# Ethernet1_RMII.net
KiCad netlist of a schematic drawn in Altium Designer
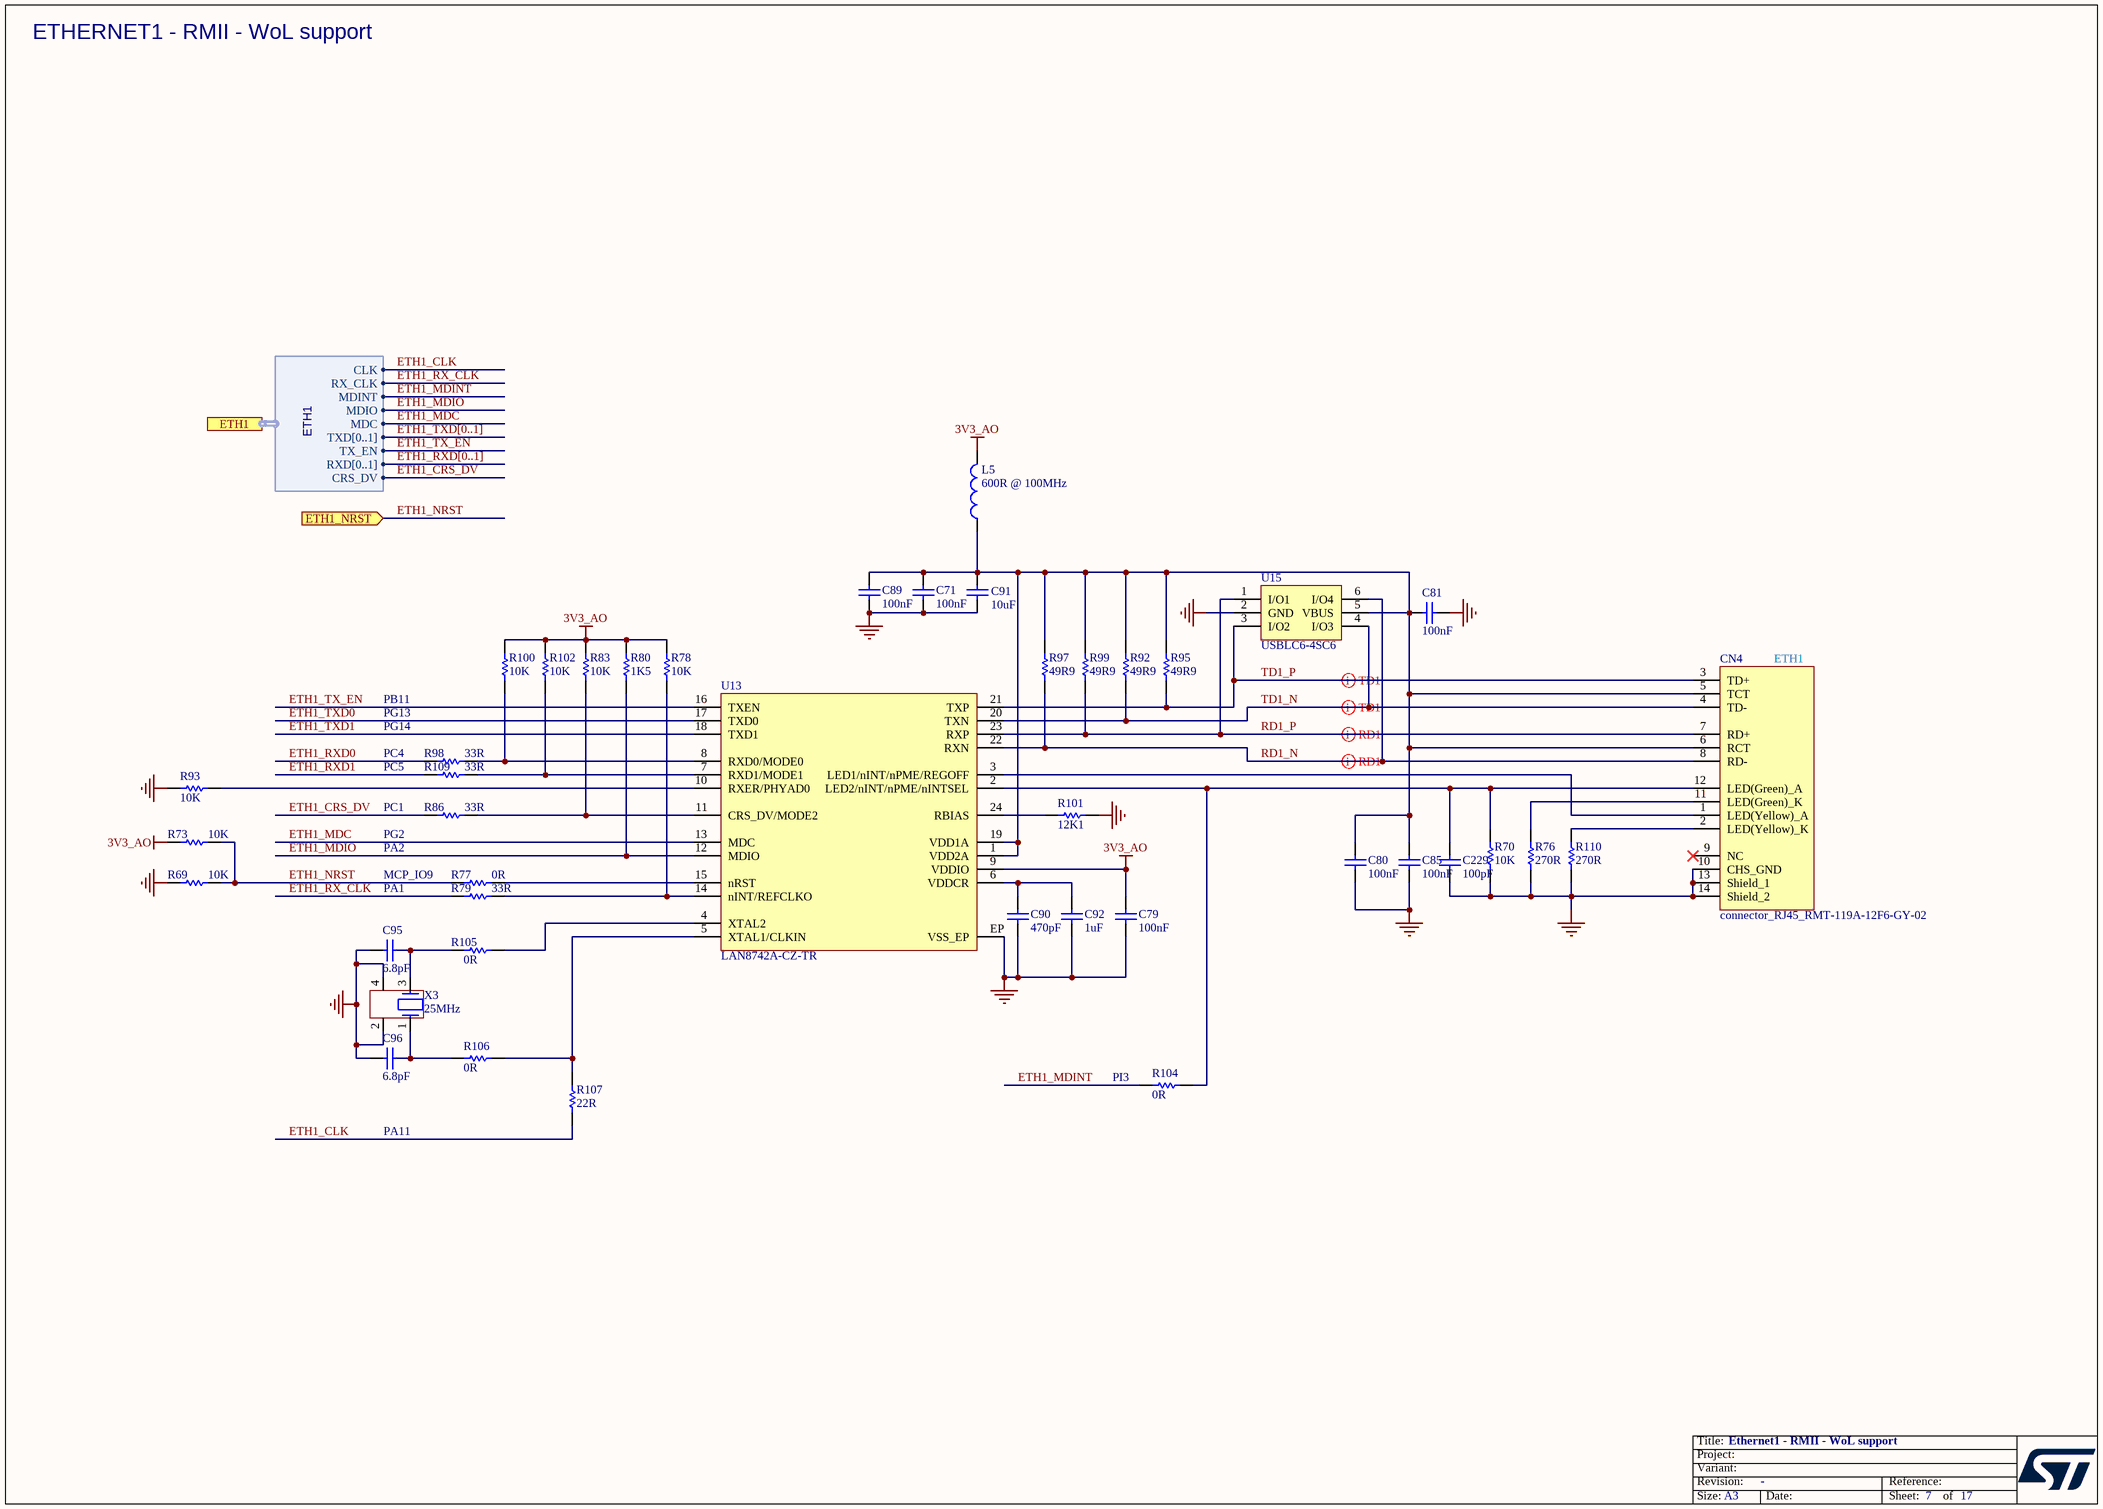
[diagram p0: Ethernet1_RMII.SchDoc]

(export (version "E")
  (design (tool "Eeschema 10.0.6"))
  (components
    (comp (ref "C71")
      (value "100nF")
      (footprint "C0402")
      (description "Capacitor, MLCC, 100nF, 16V, X7R, +/-10%, 0402, T=0.5mm")
      (fields
        (field (name "INTERNAL_PART_NUMBER") "MCD-00006")
        (field (name "MANUFACTURER_PART_NUMBER") "CC0402KRX7R7BB104")
      )
      (libsource (lib "MCD_PARTS_database") (part "Capacitor"))
    )
    (comp (ref "C79")
      (value "100nF")
      (footprint "C0402")
      (description "Capacitor, MLCC, 100nF, 16V, X7R, +/-10%, 0402, T=0.5mm")
      (fields
        (field (name "INTERNAL_PART_NUMBER") "MCD-00006")
        (field (name "MANUFACTURER_PART_NUMBER") "CC0402KRX7R7BB104")
      )
      (libsource (lib "MCD_PARTS_database") (part "Capacitor"))
    )
    (comp (ref "C80")
      (value "100nF")
      (footprint "C0402")
      (description "Capacitor, MLCC, 100nF, 16V, X7R, +/-10%, 0402, T=0.5mm")
      (fields
        (field (name "INTERNAL_PART_NUMBER") "MCD-00006")
        (field (name "MANUFACTURER_PART_NUMBER") "CC0402KRX7R7BB104")
      )
      (libsource (lib "MCD_PARTS_database") (part "Capacitor"))
    )
    (comp (ref "C81")
      (value "100nF")
      (footprint "C0402")
      (description "Capacitor, MLCC, 100nF, 16V, X7R, +/-10%, 0402, T=0.5mm")
      (fields
        (field (name "INTERNAL_PART_NUMBER") "MCD-00006")
        (field (name "MANUFACTURER_PART_NUMBER") "CC0402KRX7R7BB104")
      )
      (libsource (lib "MCD_PARTS_database") (part "Capacitor"))
    )
    (comp (ref "C85")
      (value "100nF")
      (footprint "C0402")
      (description "Capacitor, MLCC, 100nF, 16V, X7R, +/-10%, 0402, T=0.5mm")
      (fields
        (field (name "INTERNAL_PART_NUMBER") "MCD-00006")
        (field (name "MANUFACTURER_PART_NUMBER") "CC0402KRX7R7BB104")
      )
      (libsource (lib "MCD_PARTS_database") (part "Capacitor"))
    )
    (comp (ref "C89")
      (value "100nF")
      (footprint "C0402")
      (description "Capacitor, MLCC, 100nF, 16V, X7R, +/-10%, 0402, T=0.5mm")
      (fields
        (field (name "INTERNAL_PART_NUMBER") "MCD-00006")
        (field (name "MANUFACTURER_PART_NUMBER") "CC0402KRX7R7BB104")
      )
      (libsource (lib "MCD_PARTS_database") (part "Capacitor"))
    )
    (comp (ref "C90")
      (value "470pF")
      (footprint "C0402")
      (description "Capacitor, MLCC, 470pF, 50V, NPO, +/-5%, 0402, T=0.5mm")
      (fields
        (field (name "INTERNAL_PART_NUMBER") "MCD-00724")
        (field (name "MANUFACTURER_PART_NUMBER") "CC0402JRNPO9BN471")
      )
      (libsource (lib "MCD_PARTS_database") (part "Capacitor"))
    )
    (comp (ref "C91")
      (value "10uF")
      (footprint "C0603")
      (description "Capacitor, MLCC, 10uF, 10V, X5R, +/-10%, 0603, T=0.8mm")
      (fields
        (field (name "INTERNAL_PART_NUMBER") "MCD-00099")
        (field (name "MANUFACTURER_PART_NUMBER") "GRM188R61A106KE69D")
      )
      (libsource (lib "MCD_PARTS_database") (part "Capacitor"))
    )
    (comp (ref "C92")
      (value "1uF")
      (footprint "C0201_MURATA_GRM033_H0P3")
      (description "Capacitor, MLCC, 1uF, 6.3V, X5R, +/-20%, 0201, T=0,3mm")
      (fields
        (field (name "INTERNAL_PART_NUMBER") "MCD-02377")
        (field (name "MANUFACTURER_PART_NUMBER") "GRM033R60J105MEA2")
      )
      (libsource (lib "MCD_PARTS_database") (part "Capacitor"))
    )
    (comp (ref "C95")
      (value "6.8pF")
      (footprint "C0402")
      (description "Capacitor, MLCC, 6.8pF, 50V, NPO, +/-0.25pF, 0402, T=0.5mm")
      (fields
        (field (name "INTERNAL_PART_NUMBER") "MCD-00674")
        (field (name "MANUFACTURER_PART_NUMBER") "CC0402CRNPO9BN6R8")
      )
      (libsource (lib "MCD_PARTS_database") (part "Capacitor"))
    )
    (comp (ref "C96")
      (value "6.8pF")
      (footprint "C0402")
      (description "Capacitor, MLCC, 6.8pF, 50V, NPO, +/-0.25pF, 0402, T=0.5mm")
      (fields
        (field (name "INTERNAL_PART_NUMBER") "MCD-00674")
        (field (name "MANUFACTURER_PART_NUMBER") "CC0402CRNPO9BN6R8")
      )
      (libsource (lib "MCD_PARTS_database") (part "Capacitor"))
    )
    (comp (ref "C229")
      (value "100pF")
      (footprint "C0402")
      (description "Capacitor, MLCC, 100pF, 50V, NPO, +/-5%, 0402, T=0.5mm")
      (fields
        (field (name "INTERNAL_PART_NUMBER") "MCD-00205")
        (field (name "MANUFACTURER_PART_NUMBER") "CC0402JRNPO9BN101")
      )
      (libsource (lib "MCD_PARTS_database") (part "Capacitor"))
    )
    (comp (ref "CN4")
      (value "connector_RJ45_RMT-119A-12F6-GY-02")
      (footprint "CON_RJ45_PHC_RMT-119A-12F6-GY-02")
      (description "connector_RJ45, 10/100 Ethernet integrated MAG with integrate Green and Yellow LED, T= 13.61mm")
      (fields (field (name "INTERNAL_PART_NUMBER") "MCD-02475") (field (name "MANUFACTURER") "PENGHUI"))
      (libsource (lib "MCD_PARTS_database") (part "RJ45_RTS-119A-12F6-GY-02"))
    )
    (comp (ref "L5")
      (value "600R @ 100MHz")
      (footprint "L0603")
      (description "Ferrite bead, 600R @1 00MHz, +/-25%, 350mA, 0R5, 0603, T=0.8mm")
      (fields
        (field (name "INTERNAL_PART_NUMBER") "MCD-00047")
        (field (name "MANUFACTURER_PART_NUMBER") "FCM1608KF-601T03")
      )
      (libsource (lib "MCD_PARTS_database") (part "BEAD"))
    )
    (comp (ref "R69")
      (value "10K")
      (footprint "R0402")
      (description "Resistor, 10K, 0402, +/-1%, 1/16W")
      (fields
        (field (name "INTERNAL_PART_NUMBER") "MCD-00053")
        (field (name "MANUFACTURER_PART_NUMBER") "RC0402FR-0710KL")
      )
      (libsource (lib "MCD_PARTS_database") (part "Resistor"))
    )
    (comp (ref "R70")
      (value "10K")
      (footprint "R0402")
      (description "Resistor, 10K, 0402, +/-1%, 1/16W")
      (fields
        (field (name "INTERNAL_PART_NUMBER") "MCD-00053")
        (field (name "MANUFACTURER_PART_NUMBER") "RC0402FR-0710KL")
      )
      (libsource (lib "MCD_PARTS_database") (part "Resistor"))
    )
    (comp (ref "R73")
      (value "10K")
      (footprint "R0402")
      (description "Resistor, 10K, 0402, +/-1%, 1/16W")
      (fields
        (field (name "INTERNAL_PART_NUMBER") "MCD-00053")
        (field (name "MANUFACTURER_PART_NUMBER") "RC0402FR-0710KL")
      )
      (libsource (lib "MCD_PARTS_database") (part "Resistor"))
    )
    (comp (ref "R76")
      (value "270R")
      (footprint "R0402")
      (description "Resistor, 270R, 0402, +/-1%, 1/16W")
      (fields
        (field (name "INTERNAL_PART_NUMBER") "MCD-00441")
        (field (name "MANUFACTURER_PART_NUMBER") "RC0402FR-07270RL")
      )
      (libsource (lib "MCD_PARTS_database") (part "Resistor"))
    )
    (comp (ref "R77")
      (value "0R")
      (footprint "R0402")
      (description "Resistor, 0R, 0402, +/-5%, 1/16W")
      (fields (field (name "INTERNAL_PART_NUMBER") "MCD-00052") (field (name "MANUFACTURER") "YAGEO"))
      (libsource (lib "MCD_PARTS_database") (part "Resistor"))
    )
    (comp (ref "R78")
      (value "10K")
      (footprint "R0402")
      (description "Resistor, 10K, 0402, +/-1%, 1/16W")
      (fields
        (field (name "INTERNAL_PART_NUMBER") "MCD-00053")
        (field (name "MANUFACTURER_PART_NUMBER") "RC0402FR-0710KL")
      )
      (libsource (lib "MCD_PARTS_database") (part "Resistor"))
    )
    (comp (ref "R79")
      (value "33R")
      (footprint "R0402")
      (description "Resistor, 33R, 0402, +/-1%, 1/16W")
      (fields
        (field (name "INTERNAL_PART_NUMBER") "MCD-00455")
        (field (name "MANUFACTURER_PART_NUMBER") "RC0402FR-0733RL")
      )
      (libsource (lib "MCD_PARTS_database") (part "Resistor"))
    )
    (comp (ref "R80")
      (value "1K5")
      (footprint "R0402")
      (description "Resistor, 1K5, 0402, +/-1%, 1/16W")
      (fields
        (field (name "INTERNAL_PART_NUMBER") "MCD-00068")
        (field (name "MANUFACTURER_PART_NUMBER") "RC0402FR-071K5L")
      )
      (libsource (lib "MCD_PARTS_database") (part "Resistor"))
    )
    (comp (ref "R83")
      (value "10K")
      (footprint "R0402")
      (description "Resistor, 10K, 0402, +/-1%, 1/16W")
      (fields
        (field (name "INTERNAL_PART_NUMBER") "MCD-00053")
        (field (name "MANUFACTURER_PART_NUMBER") "RC0402FR-0710KL")
      )
      (libsource (lib "MCD_PARTS_database") (part "Resistor"))
    )
    (comp (ref "R86")
      (value "33R")
      (footprint "R0402")
      (description "Resistor, 33R, 0402, +/-1%, 1/16W")
      (fields
        (field (name "INTERNAL_PART_NUMBER") "MCD-00455")
        (field (name "MANUFACTURER_PART_NUMBER") "RC0402FR-0733RL")
      )
      (libsource (lib "MCD_PARTS_database") (part "Resistor"))
    )
    (comp (ref "R92")
      (value "49R9")
      (footprint "R0402")
      (description "Resistor, 49R9, 0402, +/-1%, 1/16W")
      (fields
        (field (name "INTERNAL_PART_NUMBER") "MCD-00565")
        (field (name "MANUFACTURER_PART_NUMBER") "RC0402FR-0749R9L")
      )
      (libsource (lib "MCD_PARTS_database") (part "Resistor"))
    )
    (comp (ref "R93")
      (value "10K")
      (footprint "R0402")
      (description "Resistor, 10K, 0402, +/-1%, 1/16W")
      (fields
        (field (name "INTERNAL_PART_NUMBER") "MCD-00053")
        (field (name "MANUFACTURER_PART_NUMBER") "RC0402FR-0710KL")
      )
      (libsource (lib "MCD_PARTS_database") (part "Resistor"))
    )
    (comp (ref "R95")
      (value "49R9")
      (footprint "R0402")
      (description "Resistor, 49R9, 0402, +/-1%, 1/16W")
      (fields
        (field (name "INTERNAL_PART_NUMBER") "MCD-00565")
        (field (name "MANUFACTURER_PART_NUMBER") "RC0402FR-0749R9L")
      )
      (libsource (lib "MCD_PARTS_database") (part "Resistor"))
    )
    (comp (ref "R97")
      (value "49R9")
      (footprint "R0402")
      (description "Resistor, 49R9, 0402, +/-1%, 1/16W")
      (fields
        (field (name "INTERNAL_PART_NUMBER") "MCD-00565")
        (field (name "MANUFACTURER_PART_NUMBER") "RC0402FR-0749R9L")
      )
      (libsource (lib "MCD_PARTS_database") (part "Resistor"))
    )
    (comp (ref "R98")
      (value "33R")
      (footprint "R0402")
      (description "Resistor, 33R, 0402, +/-1%, 1/16W")
      (fields
        (field (name "INTERNAL_PART_NUMBER") "MCD-00455")
        (field (name "MANUFACTURER_PART_NUMBER") "RC0402FR-0733RL")
      )
      (libsource (lib "MCD_PARTS_database") (part "Resistor"))
    )
    (comp (ref "R99")
      (value "49R9")
      (footprint "R0402")
      (description "Resistor, 49R9, 0402, +/-1%, 1/16W")
      (fields
        (field (name "INTERNAL_PART_NUMBER") "MCD-00565")
        (field (name "MANUFACTURER_PART_NUMBER") "RC0402FR-0749R9L")
      )
      (libsource (lib "MCD_PARTS_database") (part "Resistor"))
    )
    (comp (ref "R100")
      (value "10K")
      (footprint "R0402")
      (description "Resistor, 10K, 0402, +/-1%, 1/16W")
      (fields
        (field (name "INTERNAL_PART_NUMBER") "MCD-00053")
        (field (name "MANUFACTURER_PART_NUMBER") "RC0402FR-0710KL")
      )
      (libsource (lib "MCD_PARTS_database") (part "Resistor"))
    )
    (comp (ref "R101")
      (value "12K1")
      (footprint "R0402")
      (description "Resistor, 12K1, 0402, +/-1%, 1/16W")
      (fields
        (field (name "INTERNAL_PART_NUMBER") "MCD-00723")
        (field (name "MANUFACTURER_PART_NUMBER") "RC0402FR-0712K1L")
      )
      (libsource (lib "MCD_PARTS_database") (part "Resistor"))
    )
    (comp (ref "R102")
      (value "10K")
      (footprint "R0402")
      (description "Resistor, 10K, 0402, +/-1%, 1/16W")
      (fields
        (field (name "INTERNAL_PART_NUMBER") "MCD-00053")
        (field (name "MANUFACTURER_PART_NUMBER") "RC0402FR-0710KL")
      )
      (libsource (lib "MCD_PARTS_database") (part "Resistor"))
    )
    (comp (ref "R104")
      (value "0R")
      (footprint "R0402")
      (description "Resistor, 0R, 0402, +/-5%, 1/16W")
      (fields
        (field (name "INTERNAL_PART_NUMBER") "MCD-00052")
        (field (name "MANUFACTURER_PART_NUMBER") "RC0402JR-070RL")
      )
      (libsource (lib "MCD_PARTS_database") (part "Resistor"))
    )
    (comp (ref "R105")
      (value "0R")
      (footprint "R0402")
      (description "Resistor, 0R, 0402, +/-5%, 1/16W")
      (fields
        (field (name "INTERNAL_PART_NUMBER") "MCD-00052")
        (field (name "MANUFACTURER_PART_NUMBER") "RC0402JR-070RL")
      )
      (libsource (lib "MCD_PARTS_database") (part "Resistor"))
    )
    (comp (ref "R106")
      (value "0R")
      (footprint "R0402")
      (description "Resistor, 0R, 0402, +/-5%, 1/16W")
      (fields
        (field (name "INTERNAL_PART_NUMBER") "MCD-00052")
        (field (name "MANUFACTURER_PART_NUMBER") "RC0402JR-070RL")
      )
      (libsource (lib "MCD_PARTS_database") (part "Resistor"))
    )
    (comp (ref "R107")
      (value "22R")
      (footprint "R0402")
      (description "Resistor, 22R, 0402, +/-1%, 1/16W")
      (fields
        (field (name "INTERNAL_PART_NUMBER") "MCD-00189")
        (field (name "MANUFACTURER_PART_NUMBER") "RC0402FR-0722RL")
      )
      (libsource (lib "MCD_PARTS_database") (part "Resistor"))
    )
    (comp (ref "R109")
      (value "33R")
      (footprint "R0402")
      (description "Resistor, 33R, 0402, +/-1%, 1/16W")
      (fields
        (field (name "INTERNAL_PART_NUMBER") "MCD-00455")
        (field (name "MANUFACTURER_PART_NUMBER") "RC0402FR-0733RL")
      )
      (libsource (lib "MCD_PARTS_database") (part "Resistor"))
    )
    (comp (ref "R110")
      (value "270R")
      (footprint "R0402")
      (description "Resistor, 270R, 0402, +/-1%, 1/16W")
      (fields
        (field (name "INTERNAL_PART_NUMBER") "MCD-00441")
        (field (name "MANUFACTURER_PART_NUMBER") "RC0402FR-07270RL")
      )
      (libsource (lib "MCD_PARTS_database") (part "Resistor"))
    )
    (comp (ref "U13")
      (value "LAN8742A-CZ-TR")
      (footprint "ICC_VQFN24-EPAD_4X4_P050")
      (description "10/100M RMII Ethernet transceiver")
      (fields (field (name "INTERNAL_PART_NUMBER") "MCD-00719") (field (name "MANUFACTURER") "MICROCHIP"))
      (libsource (lib "MCD_PARTS_database") (part "LAN8742A-CZ-TR"))
    )
    (comp (ref "U15")
      (value "USBLC6-4SC6")
      (footprint "ESD_SOT23-6L")
      (description "Very low capacitance ESD protection , 4 lines")
      (fields
        (field (name "INTERNAL_PART_NUMBER") "MCD-00250")
        (field (name "MANUFACTURER") "STMICROELECTRONICS")
      )
      (libsource (lib "MCD_PARTS_database") (part "USBLC6-4SC6"))
    )
    (comp (ref "X3")
      (value "25MHz")
      (footprint "CRY_NX2016SA_4P")
      (description "Crystal, 25MHz, 6pF, +/-20ppm, 80R, 2x1.6mm")
      (fields (field (name "INTERNAL_PART_NUMBER") "MCD-01364") (field (name "BMS_PART_NUMBER") "9157044"))
      (libsource (lib "MCD_PARTS_database") (part "XTAL_4_PINS"))
    )
  )
  (nets
    (net (code "2") (name "/ETH1_CLK") (class "Default")
      (node (ref "R107") (pin "1") (pinfunction "1_1") (pintype "passive"))
    )
    (net (code "3") (name "/ETH1_CRS_DV") (class "Default")
      (node (ref "R86") (pin "1") (pinfunction "1_1") (pintype "passive"))
    )
    (net (code "4") (name "/ETH1_MDC") (class "Default")
      (node (ref "U13") (pin "13") (pinfunction "MDC_13") (pintype "passive"))
    )
    (net (code "5") (name "/ETH1_MDINT") (class "Default")
      (node (ref "R104") (pin "1") (pinfunction "1_1") (pintype "passive"))
    )
    (net (code "6") (name "/ETH1_MDIO") (class "Default")
      (node (ref "R80") (pin "1") (pinfunction "1_1") (pintype "passive"))
      (node (ref "U13") (pin "12") (pinfunction "MDIO_12") (pintype "passive"))
    )
    (net (code "7") (name "/ETH1_NRST") (class "Default")
      (node (ref "R69") (pin "1") (pinfunction "1_1") (pintype "passive"))
      (node (ref "R73") (pin "1") (pinfunction "1_1") (pintype "passive"))
      (node (ref "R77") (pin "1") (pinfunction "1_1") (pintype "passive"))
    )
    (net (code "8") (name "/ETH1_RXD0") (class "Default")
      (node (ref "R98") (pin "1") (pinfunction "1_1") (pintype "passive"))
    )
    (net (code "9") (name "/ETH1_RXD1") (class "Default")
      (node (ref "R109") (pin "1") (pinfunction "1_1") (pintype "passive"))
    )
    (net (code "11") (name "/ETH1_RX_CLK") (class "Default")
      (node (ref "R79") (pin "1") (pinfunction "1_1") (pintype "passive"))
    )
    (net (code "12") (name "/ETH1_TXD0") (class "Default")
      (node (ref "U13") (pin "17") (pinfunction "TXD0_17") (pintype "passive"))
    )
    (net (code "13") (name "/ETH1_TXD1") (class "Default")
      (node (ref "U13") (pin "18") (pinfunction "TXD1_18") (pintype "passive"))
    )
    (net (code "14") (name "/ETH1_TX_EN") (class "Default")
      (node (ref "U13") (pin "16") (pinfunction "TXEN_16") (pintype "passive"))
    )
    (net (code "16") (name "/RD1_N") (class "Default")
      (node (ref "CN4") (pin "8") (pinfunction "RD-_8") (pintype "passive"))
      (node (ref "R97") (pin "1") (pinfunction "1_1") (pintype "passive"))
      (node (ref "U13") (pin "22") (pinfunction "RXN_22") (pintype "passive"))
      (node (ref "U15") (pin "6") (pinfunction "I/O4_6") (pintype "passive"))
    )
    (net (code "17") (name "/RD1_P") (class "Default")
      (node (ref "CN4") (pin "7") (pinfunction "RD+_7") (pintype "passive"))
      (node (ref "R99") (pin "1") (pinfunction "1_1") (pintype "passive"))
      (node (ref "U13") (pin "23") (pinfunction "RXP_23") (pintype "passive"))
      (node (ref "U15") (pin "1") (pinfunction "I/O1_1") (pintype "passive"))
    )
    (net (code "18") (name "/TD1_N") (class "Default")
      (node (ref "CN4") (pin "4") (pinfunction "TD-_4") (pintype "passive"))
      (node (ref "R92") (pin "1") (pinfunction "1_1") (pintype "passive"))
      (node (ref "U13") (pin "20") (pinfunction "TXN_20") (pintype "passive"))
      (node (ref "U15") (pin "4") (pinfunction "I/O3_4") (pintype "passive"))
    )
    (net (code "19") (name "/TD1_P") (class "Default")
      (node (ref "CN4") (pin "3") (pinfunction "TD+_3") (pintype "passive"))
      (node (ref "R95") (pin "1") (pinfunction "1_1") (pintype "passive"))
      (node (ref "U13") (pin "21") (pinfunction "TXP_21") (pintype "passive"))
      (node (ref "U15") (pin "3") (pinfunction "I/O2_3") (pintype "passive"))
    )
    (net (code "20") (name "3V3_AO") (class "Default")
      (node (ref "C79") (pin "2") (pinfunction "2_2") (pintype "passive"))
      (node (ref "L5") (pin "2") (pinfunction "2_2") (pintype "passive"))
      (node (ref "R100") (pin "2") (pinfunction "2_2") (pintype "passive"))
      (node (ref "R102") (pin "2") (pinfunction "2_2") (pintype "passive"))
      (node (ref "R73") (pin "2") (pinfunction "2_2") (pintype "passive"))
      (node (ref "R78") (pin "2") (pinfunction "2_2") (pintype "passive"))
      (node (ref "R80") (pin "2") (pinfunction "2_2") (pintype "passive"))
      (node (ref "R83") (pin "2") (pinfunction "2_2") (pintype "passive"))
      (node (ref "U13") (pin "9") (pinfunction "VDDIO_9") (pintype "passive"))
    )
    (net (code "21") (name "GND") (class "Default")
      (node (ref "C229") (pin "1") (pinfunction "1_1") (pintype "passive"))
      (node (ref "C71") (pin "1") (pinfunction "1_1") (pintype "passive"))
      (node (ref "C79") (pin "1") (pinfunction "1_1") (pintype "passive"))
      (node (ref "C80") (pin "1") (pinfunction "1_1") (pintype "passive"))
      (node (ref "C81") (pin "2") (pinfunction "2_2") (pintype "passive"))
      (node (ref "C85") (pin "1") (pinfunction "1_1") (pintype "passive"))
      (node (ref "C89") (pin "1") (pinfunction "1_1") (pintype "passive"))
      (node (ref "C90") (pin "1") (pinfunction "1_1") (pintype "passive"))
      (node (ref "C91") (pin "2") (pinfunction "2_2") (pintype "passive"))
      (node (ref "C92") (pin "1") (pinfunction "1_1") (pintype "passive"))
      (node (ref "C95") (pin "1") (pinfunction "1_1") (pintype "passive"))
      (node (ref "C96") (pin "1") (pinfunction "1_1") (pintype "passive"))
      (node (ref "CN4") (pin "10") (pinfunction "CHS_GND_10") (pintype "passive"))
      (node (ref "CN4") (pin "13") (pinfunction "Shield_1_13") (pintype "passive"))
      (node (ref "CN4") (pin "14") (pinfunction "Shield_2_14") (pintype "passive"))
      (node (ref "R101") (pin "2") (pinfunction "2_2") (pintype "passive"))
      (node (ref "R110") (pin "1") (pinfunction "1_1") (pintype "passive"))
      (node (ref "R69") (pin "2") (pinfunction "2_2") (pintype "passive"))
      (node (ref "R70") (pin "1") (pinfunction "1_1") (pintype "passive"))
      (node (ref "R76") (pin "1") (pinfunction "1_1") (pintype "passive"))
      (node (ref "R93") (pin "2") (pinfunction "2_2") (pintype "passive"))
      (node (ref "U13") (pin "EP") (pinfunction "VSS_EP_EP") (pintype "passive"))
      (node (ref "U15") (pin "2") (pinfunction "GND_2") (pintype "passive"))
      (node (ref "X3") (pin "2") (pinfunction "2_2") (pintype "passive"))
      (node (ref "X3") (pin "4") (pinfunction "4_4") (pintype "passive"))
    )
    (net (code "22") (name "Net-(C95-Pad2)") (class "Default")
      (node (ref "C95") (pin "2") (pinfunction "2_2") (pintype "passive"))
      (node (ref "R105") (pin "1") (pinfunction "1_1") (pintype "passive"))
      (node (ref "X3") (pin "3") (pinfunction "3_3") (pintype "passive"))
    )
    (net (code "23") (name "Net-(C96-Pad2)") (class "Default")
      (node (ref "C96") (pin "2") (pinfunction "2_2") (pintype "passive"))
      (node (ref "R106") (pin "1") (pinfunction "1_1") (pintype "passive"))
      (node (ref "X3") (pin "1") (pinfunction "1_1") (pintype "passive"))
    )
    (net (code "24") (name "Net-(CN4-LED(Green)_A)") (class "Default")
      (node (ref "C229") (pin "2") (pinfunction "2_2") (pintype "passive"))
      (node (ref "CN4") (pin "12") (pinfunction "LED(Green)_A_12") (pintype "passive"))
      (node (ref "R104") (pin "2") (pinfunction "2_2") (pintype "passive"))
      (node (ref "R70") (pin "2") (pinfunction "2_2") (pintype "passive"))
      (node (ref "U13") (pin "2") (pinfunction "LED2/nINT/nPME/nINTSEL_2") (pintype "passive"))
    )
    (net (code "25") (name "Net-(CN4-LED(Green)_K)") (class "Default")
      (node (ref "CN4") (pin "11") (pinfunction "LED(Green)_K_11") (pintype "passive"))
      (node (ref "R76") (pin "2") (pinfunction "2_2") (pintype "passive"))
    )
    (net (code "26") (name "Net-(CN4-LED(Yellow)_A)") (class "Default")
      (node (ref "CN4") (pin "1") (pinfunction "LED(Yellow)_A_1") (pintype "passive"))
      (node (ref "U13") (pin "3") (pinfunction "LED1/nINT/nPME/REGOFF_3") (pintype "passive"))
    )
    (net (code "27") (name "Net-(CN4-LED(Yellow)_K)") (class "Default")
      (node (ref "CN4") (pin "2") (pinfunction "LED(Yellow)_K_2") (pintype "passive"))
      (node (ref "R110") (pin "2") (pinfunction "2_2") (pintype "passive"))
    )
    (net (code "28") (name "Net-(CN4-RCT)") (class "Default")
      (node (ref "C71") (pin "2") (pinfunction "2_2") (pintype "passive"))
      (node (ref "C80") (pin "2") (pinfunction "2_2") (pintype "passive"))
      (node (ref "C81") (pin "1") (pinfunction "1_1") (pintype "passive"))
      (node (ref "C85") (pin "2") (pinfunction "2_2") (pintype "passive"))
      (node (ref "C89") (pin "2") (pinfunction "2_2") (pintype "passive"))
      (node (ref "C91") (pin "1") (pinfunction "1_1") (pintype "passive"))
      (node (ref "CN4") (pin "5") (pinfunction "TCT_5") (pintype "passive"))
      (node (ref "CN4") (pin "6") (pinfunction "RCT_6") (pintype "passive"))
      (node (ref "L5") (pin "1") (pinfunction "1_1") (pintype "passive"))
      (node (ref "R92") (pin "2") (pinfunction "2_2") (pintype "passive"))
      (node (ref "R95") (pin "2") (pinfunction "2_2") (pintype "passive"))
      (node (ref "R97") (pin "2") (pinfunction "2_2") (pintype "passive"))
      (node (ref "R99") (pin "2") (pinfunction "2_2") (pintype "passive"))
      (node (ref "U13") (pin "1") (pinfunction "VDD2A_1") (pintype "passive"))
      (node (ref "U13") (pin "19") (pinfunction "VDD1A_19") (pintype "passive"))
      (node (ref "U15") (pin "5") (pinfunction "VBUS_5") (pintype "passive"))
    )
    (net (code "29") (name "Net-(U13-CRS_DV{slash}MODE2)") (class "Default")
      (node (ref "R83") (pin "1") (pinfunction "1_1") (pintype "passive"))
      (node (ref "R86") (pin "2") (pinfunction "2_2") (pintype "passive"))
      (node (ref "U13") (pin "11") (pinfunction "CRS_DV/MODE2_11") (pintype "passive"))
    )
    (net (code "30") (name "Net-(U13-RBIAS)") (class "Default")
      (node (ref "R101") (pin "1") (pinfunction "1_1") (pintype "passive"))
      (node (ref "U13") (pin "24") (pinfunction "RBIAS_24") (pintype "passive"))
    )
    (net (code "31") (name "Net-(U13-RXD0{slash}MODE0)") (class "Default")
      (node (ref "R100") (pin "1") (pinfunction "1_1") (pintype "passive"))
      (node (ref "R98") (pin "2") (pinfunction "2_2") (pintype "passive"))
      (node (ref "U13") (pin "8") (pinfunction "RXD0/MODE0_8") (pintype "passive"))
    )
    (net (code "32") (name "Net-(U13-RXD1{slash}MODE1)") (class "Default")
      (node (ref "R102") (pin "1") (pinfunction "1_1") (pintype "passive"))
      (node (ref "R109") (pin "2") (pinfunction "2_2") (pintype "passive"))
      (node (ref "U13") (pin "7") (pinfunction "RXD1/MODE1_7") (pintype "passive"))
    )
    (net (code "33") (name "Net-(U13-RXER{slash}PHYAD0)") (class "Default")
      (node (ref "R93") (pin "1") (pinfunction "1_1") (pintype "passive"))
      (node (ref "U13") (pin "10") (pinfunction "RXER/PHYAD0_10") (pintype "passive"))
    )
    (net (code "34") (name "Net-(U13-VDDCR)") (class "Default")
      (node (ref "C90") (pin "2") (pinfunction "2_2") (pintype "passive"))
      (node (ref "C92") (pin "2") (pinfunction "2_2") (pintype "passive"))
      (node (ref "U13") (pin "6") (pinfunction "VDDCR_6") (pintype "passive"))
    )
    (net (code "35") (name "Net-(U13-XTAL1{slash}CLKIN)") (class "Default")
      (node (ref "R106") (pin "2") (pinfunction "2_2") (pintype "passive"))
      (node (ref "R107") (pin "2") (pinfunction "2_2") (pintype "passive"))
      (node (ref "U13") (pin "5") (pinfunction "XTAL1/CLKIN_5") (pintype "passive"))
    )
    (net (code "36") (name "Net-(U13-XTAL2)") (class "Default")
      (node (ref "R105") (pin "2") (pinfunction "2_2") (pintype "passive"))
      (node (ref "U13") (pin "4") (pinfunction "XTAL2_4") (pintype "passive"))
    )
    (net (code "37") (name "Net-(U13-nINT{slash}REFCLKO)") (class "Default")
      (node (ref "R78") (pin "1") (pinfunction "1_1") (pintype "passive"))
      (node (ref "R79") (pin "2") (pinfunction "2_2") (pintype "passive"))
      (node (ref "U13") (pin "14") (pinfunction "nINT/REFCLKO_14") (pintype "passive"))
    )
    (net (code "38") (name "Net-(U13-nRST)") (class "Default")
      (node (ref "R77") (pin "2") (pinfunction "2_2") (pintype "passive"))
      (node (ref "U13") (pin "15") (pinfunction "nRST_15") (pintype "passive"))
    )
    (net (code "39") (name "unconnected-(CN4-NC-Pad9)") (class "Default")
      (node (ref "CN4") (pin "9") (pinfunction "NC_9") (pintype "passive+no_connect"))
    )
  )
)
